# GPS.net
KiCad netlist of a schematic drawn in Altium Designer
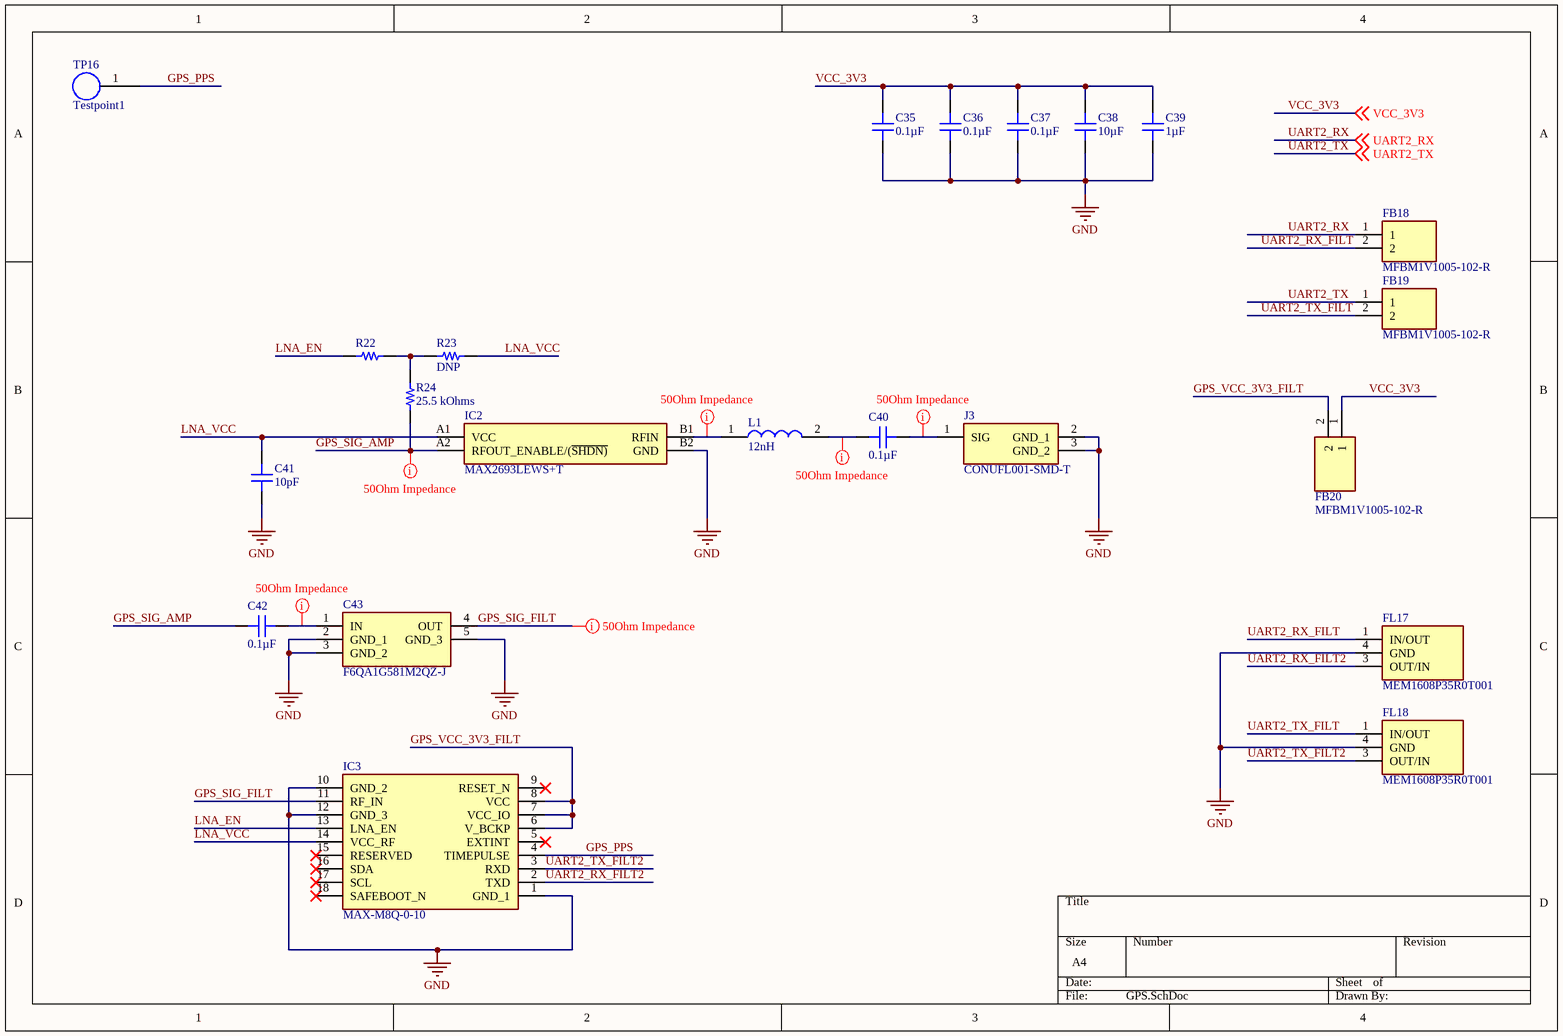
[diagram p0: GPS.SchDoc]

(export (version "E")
  (design (tool "Eeschema 10.0.6"))
  (components
    (comp (ref "C35")
      (value "0.1µF")
      (footprint "CAP 0402_1005")
      (description "CAP CER 0.1UF 6.3V X5R 0402")
      (fields (field (name "PART NUMBER") "C0402C104K9PACTU") (field (name "MANUFACTURER") "KEMET"))
      (libsource (lib "Celestial Altium Library - altium_library") (part "Capacitor"))
    )
    (comp (ref "C36")
      (value "0.1µF")
      (footprint "CAP 0402_1005")
      (description "CAP CER 0.1UF 6.3V X5R 0402")
      (fields (field (name "PART NUMBER") "C0402C104K9PACTU") (field (name "MANUFACTURER") "KEMET"))
      (libsource (lib "Celestial Altium Library - altium_library") (part "Capacitor"))
    )
    (comp (ref "C37")
      (value "0.1µF")
      (footprint "CAP 0402_1005")
      (description "CAP CER 0.1UF 6.3V X5R 0402")
      (fields (field (name "PART NUMBER") "C0402C104K9PACTU") (field (name "MANUFACTURER") "KEMET"))
      (libsource (lib "Celestial Altium Library - altium_library") (part "Capacitor"))
    )
    (comp (ref "C38")
      (value "10µF")
      (footprint "CAP 0402_1005")
      (description "CAP CER 10UF 6.3V X5R 0402")
      (fields (field (name "PART NUMBER") "C0402C106M9PAC7867") (field (name "MANUFACTURER") "KEMET"))
      (libsource (lib "Celestial Altium Library - altium_library") (part "Capacitor"))
    )
    (comp (ref "C39")
      (value "1µF")
      (footprint "CAP 0402_1005")
      (description "CAP CER 1UF 16V X5R 0402")
      (fields (field (name "PART NUMBER") "0402YD105KAT2A") (field (name "MANUFACTURER") "AVX Corporation"))
      (libsource (lib "Celestial Altium Library - altium_library") (part "Capacitor"))
    )
    (comp (ref "C40")
      (value "0.1µF")
      (footprint "CAP 0402_1005")
      (description "CAP CER 0.1UF 6.3V X5R 0402")
      (fields (field (name "PART NUMBER") "C0402C104K9PACTU") (field (name "MANUFACTURER") "KEMET"))
      (libsource (lib "Celestial Altium Library - altium_library") (part "Capacitor"))
    )
    (comp (ref "C41")
      (value "10pF")
      (footprint "CAP 0402_1005")
      (description "CAP CER 10PF 50V C0G/NP0 0402")
      (fields
        (field (name "PART NUMBER") "0402N100G500CT")
        (field (name "MANUFACTURER") "Walsin Technology Corporation")
      )
      (libsource (lib "Celestial Altium Library - altium_library") (part "Capacitor"))
    )
    (comp (ref "C42")
      (value "0.1µF")
      (footprint "CAP 0402_1005")
      (description "CAP CER 0.1UF 6.3V X5R 0402")
      (fields (field (name "PART NUMBER") "C0402C104K9PACTU") (field (name "MANUFACTURER") "KEMET"))
      (libsource (lib "Celestial Altium Library - altium_library") (part "Capacitor"))
    )
    (comp (ref "C43")
      (value "F6QA1G581M2QZ-J")
      (footprint "SamacSys:F6QA1G581M2QZJ")
      (description "Capacitor")
      (libsource (lib "SamacSys") (part "F6QA1G581M2QZ-J"))
    )
    (comp (ref "FB18")
      (value "MFBM1V1005-102-R")
      (footprint "SamacSys:BEADC1005X65N")
      (description "Ferrite Bead")
      (fields (field (name "MANUFACTURER_PART_NUMBER") "MFBM1V1005-101-R"))
      (libsource (lib "SamacSys") (part "MFBM1V1005-102-R"))
    )
    (comp (ref "FB19")
      (value "MFBM1V1005-102-R")
      (footprint "SamacSys:BEADC1005X65N")
      (description "Ferrite Bead")
      (fields (field (name "MANUFACTURER_PART_NUMBER") "MFBM1V1005-101-R"))
      (libsource (lib "SamacSys") (part "MFBM1V1005-102-R"))
    )
    (comp (ref "FB20")
      (value "MFBM1V1005-102-R")
      (footprint "SamacSys:BEADC1005X65N")
      (description "Ferrite Bead")
      (fields (field (name "MANUFACTURER_PART_NUMBER") "MFBM1V1005-101-R"))
      (libsource (lib "") (part "MFBM1V1005-102-R_1"))
    )
    (comp (ref "FL17")
      (value "MEM1608P35R0T001")
      (footprint "SamacSys:MEM1608P35R0T001")
      (description "Filter")
      (libsource (lib "SamacSys") (part "MEM1608P35R0T001"))
    )
    (comp (ref "FL18")
      (value "MEM1608P35R0T001")
      (footprint "SamacSys:MEM1608P35R0T001")
      (description "Filter")
      (libsource (lib "SamacSys") (part "MEM1608P35R0T001"))
    )
    (comp (ref "IC2")
      (value "MAX2693LEWS+T")
      (footprint "SamacSys:BGA4C40P2X2_84X84X69")
      (description "Integrated Circuit")
      (libsource (lib "*") (part "MAX2693LEWS+T"))
    )
    (comp (ref "IC3")
      (value "MAX-M8Q-0-10")
      (footprint "SamacSys:MAX-M8")
      (description "Integrated Circuit")
      (libsource (lib "SamacSys") (part "MAX-M8Q-0-10"))
    )
    (comp (ref "J3")
      (value "CONUFL001-SMD-T")
      (footprint "SamacSys:CONUFL001-SMD")
      (description "Connector")
      (fields (field (name "MOUSER2 PART NUMBER") "712-CONUFL001-SMD-T"))
      (libsource (lib "SamacSys") (part "CONUFL001-SMD-T"))
    )
    (comp (ref "L1")
      (value "12nH")
      (footprint "SamacSys:INDC1005X55N")
      (description "Inductor")
      (fields (field (name "MANUFACTURER_PART_NUMBER") "7447840112G"))
      (libsource (lib "*") (part "7447840112G"))
    )
    (comp (ref "R22")
      (value "~")
      (footprint "RES 0402_1005")
      (description "RES SMD 0 OHM JUMPER 1/16W 0402")
      (fields (field (name "PART NUMBER") "CRCW04020000Z0ED") (field (name "MANUFACTURER") "Vishay Dale"))
      (libsource (lib "Celestial Altium Library - altium_library") (part "Resistor"))
    )
    (comp (ref "R23")
      (value "~")
      (footprint "RES 0402_1005")
      (description "RES SMD 0 OHM JUMPER 1/16W 0402")
      (fields
        (field (name "PART NUMBER") "CRCW04020000Z0ED")
        (field (name "MANUFACTURER") "Vishay Dale")
        (field (name "ASSEMBLY INSTRUCTION") "DNP")
      )
      (libsource (lib "Celestial Altium Library - altium_library") (part "Resistor"))
    )
    (comp (ref "R24")
      (value "25.5 kOhms")
      (footprint "RES 0402_1005")
      (description "RES SMD 25.5K OHM 1% 1/16W 0402")
      (fields (field (name "PART NUMBER") "AC0402FR-0725K5L") (field (name "MANUFACTURER") "Yageo"))
      (libsource (lib "Celestial Altium Library - altium_library") (part "Resistor"))
    )
    (comp (ref "TP16")
      (value "Testpoint1")
      (footprint "Testpoint1")
      (libsource (lib "SamacSys") (part "Testpoint1"))
    )
  )
  (nets
    (net (code "1") (name "/GPS_PPS") (class "Default")
      (node (ref "IC3") (pin "4") (pinfunction "TIMEPULSE_4") (pintype "passive"))
      (node (ref "TP16") (pin "1") (pinfunction "1_1") (pintype "passive"))
    )
    (net (code "2") (name "/GPS_SIG_AMP") (class "Default")
      (node (ref "C42") (pin "2") (pinfunction "2_2") (pintype "passive"))
      (node (ref "IC2") (pin "A2") (pinfunction "RFOUT_ENABLE/(~{SHDN)}_A2") (pintype "passive"))
      (node (ref "R24") (pin "1") (pinfunction "1_1") (pintype "passive"))
    )
    (net (code "3") (name "/GPS_SIG_FILT") (class "Default")
      (node (ref "C43") (pin "4") (pinfunction "OUT_4") (pintype "passive"))
      (node (ref "IC3") (pin "11") (pinfunction "RF_IN_11") (pintype "passive"))
    )
    (net (code "4") (name "/GPS_VCC_3V3_FILT") (class "Default")
      (node (ref "FB20") (pin "2") (pinfunction "2_2") (pintype "passive"))
      (node (ref "IC3") (pin "6") (pinfunction "V_BCKP_6") (pintype "passive"))
      (node (ref "IC3") (pin "7") (pinfunction "VCC_IO_7") (pintype "passive"))
      (node (ref "IC3") (pin "8") (pinfunction "VCC_8") (pintype "passive"))
    )
    (net (code "5") (name "/LNA_EN") (class "Default")
      (node (ref "IC3") (pin "13") (pinfunction "LNA_EN_13") (pintype "passive"))
      (node (ref "R22") (pin "2") (pinfunction "2_2") (pintype "passive"))
    )
    (net (code "6") (name "/LNA_VCC") (class "Default")
      (node (ref "C41") (pin "2") (pinfunction "2_2") (pintype "passive"))
      (node (ref "IC2") (pin "A1") (pinfunction "VCC_A1") (pintype "passive"))
      (node (ref "IC3") (pin "14") (pinfunction "VCC_RF_14") (pintype "passive"))
      (node (ref "R23") (pin "1") (pinfunction "1_1") (pintype "passive"))
    )
    (net (code "7") (name "/UART2_RX_FILT") (class "Default")
      (node (ref "FB18") (pin "2") (pinfunction "2_2") (pintype "passive"))
      (node (ref "FL17") (pin "1") (pinfunction "IN/OUT_1") (pintype "passive"))
    )
    (net (code "8") (name "/UART2_RX_FILT2") (class "Default")
      (node (ref "FL17") (pin "3") (pinfunction "OUT/IN_3") (pintype "passive"))
      (node (ref "IC3") (pin "2") (pinfunction "TXD_2") (pintype "passive"))
    )
    (net (code "9") (name "/UART2_TX_FILT") (class "Default")
      (node (ref "FB19") (pin "2") (pinfunction "2_2") (pintype "passive"))
      (node (ref "FL18") (pin "1") (pinfunction "IN/OUT_1") (pintype "passive"))
    )
    (net (code "10") (name "/UART2_TX_FILT2") (class "Default")
      (node (ref "FL18") (pin "3") (pinfunction "OUT/IN_3") (pintype "passive"))
      (node (ref "IC3") (pin "3") (pinfunction "RXD_3") (pintype "passive"))
    )
    (net (code "11") (name "GND") (class "Default")
      (node (ref "C35") (pin "1") (pinfunction "1_1") (pintype "passive"))
      (node (ref "C36") (pin "1") (pinfunction "1_1") (pintype "passive"))
      (node (ref "C37") (pin "1") (pinfunction "1_1") (pintype "passive"))
      (node (ref "C38") (pin "1") (pinfunction "1_1") (pintype "passive"))
      (node (ref "C39") (pin "1") (pinfunction "1_1") (pintype "passive"))
      (node (ref "C41") (pin "1") (pinfunction "1_1") (pintype "passive"))
      (node (ref "C43") (pin "2") (pinfunction "GND_1_2") (pintype "passive"))
      (node (ref "C43") (pin "3") (pinfunction "GND_2_3") (pintype "passive"))
      (node (ref "C43") (pin "5") (pinfunction "GND_3_5") (pintype "passive"))
      (node (ref "FL17") (pin "4") (pinfunction "GND_4") (pintype "passive"))
      (node (ref "FL18") (pin "4") (pinfunction "GND_4") (pintype "passive"))
      (node (ref "IC2") (pin "B2") (pinfunction "GND_B2") (pintype "passive"))
      (node (ref "IC3") (pin "1") (pinfunction "GND_1_1") (pintype "passive"))
      (node (ref "IC3") (pin "10") (pinfunction "GND_2_10") (pintype "passive"))
      (node (ref "IC3") (pin "12") (pinfunction "GND_3_12") (pintype "passive"))
      (node (ref "J3") (pin "2") (pinfunction "GND_1_2") (pintype "passive"))
      (node (ref "J3") (pin "3") (pinfunction "GND_2_3") (pintype "passive"))
    )
    (net (code "12") (name "Net-(C40-Pad2)") (class "Default")
      (node (ref "C40") (pin "2") (pinfunction "2_2") (pintype "passive"))
      (node (ref "L1") (pin "2") (pinfunction "2_2") (pintype "passive"))
    )
    (net (code "13") (name "Net-(C43-IN)") (class "Default")
      (node (ref "C42") (pin "1") (pinfunction "1_1") (pintype "passive"))
      (node (ref "C43") (pin "1") (pinfunction "IN_1") (pintype "passive"))
    )
    (net (code "14") (name "Net-(IC2-RFIN)") (class "Default")
      (node (ref "IC2") (pin "B1") (pinfunction "RFIN_B1") (pintype "passive"))
      (node (ref "L1") (pin "1") (pinfunction "1_1") (pintype "passive"))
    )
    (net (code "15") (name "Net-(J3-SIG)") (class "Default")
      (node (ref "C40") (pin "1") (pinfunction "1_1") (pintype "passive"))
      (node (ref "J3") (pin "1") (pinfunction "SIG_1") (pintype "passive"))
    )
    (net (code "16") (name "Net-(R22-Pad1)") (class "Default")
      (node (ref "R22") (pin "1") (pinfunction "1_1") (pintype "passive"))
      (node (ref "R23") (pin "2") (pinfunction "2_2") (pintype "passive"))
      (node (ref "R24") (pin "2") (pinfunction "2_2") (pintype "passive"))
    )
    (net (code "17") (name "UART2_RX") (class "Default")
      (node (ref "FB18") (pin "1") (pinfunction "1_1") (pintype "passive"))
    )
    (net (code "18") (name "UART2_TX") (class "Default")
      (node (ref "FB19") (pin "1") (pinfunction "1_1") (pintype "passive"))
    )
    (net (code "19") (name "VCC_3V3") (class "Default")
      (node (ref "C35") (pin "2") (pinfunction "2_2") (pintype "passive"))
      (node (ref "C36") (pin "2") (pinfunction "2_2") (pintype "passive"))
      (node (ref "C37") (pin "2") (pinfunction "2_2") (pintype "passive"))
      (node (ref "C38") (pin "2") (pinfunction "2_2") (pintype "passive"))
      (node (ref "C39") (pin "2") (pinfunction "2_2") (pintype "passive"))
      (node (ref "FB20") (pin "1") (pinfunction "1_1") (pintype "passive"))
    )
    (net (code "20") (name "unconnected-(IC3-EXTINT-Pad5)") (class "Default")
      (node (ref "IC3") (pin "5") (pinfunction "EXTINT_5") (pintype "passive+no_connect"))
    )
    (net (code "21") (name "unconnected-(IC3-RESERVED-Pad15)") (class "Default")
      (node (ref "IC3") (pin "15") (pinfunction "RESERVED_15") (pintype "passive+no_connect"))
    )
    (net (code "22") (name "unconnected-(IC3-RESET_N-Pad9)") (class "Default")
      (node (ref "IC3") (pin "9") (pinfunction "RESET_N_9") (pintype "passive+no_connect"))
    )
    (net (code "23") (name "unconnected-(IC3-SAFEBOOT_N-Pad18)") (class "Default")
      (node (ref "IC3") (pin "18") (pinfunction "SAFEBOOT_N_18") (pintype "passive+no_connect"))
    )
    (net (code "24") (name "unconnected-(IC3-SCL-Pad17)") (class "Default")
      (node (ref "IC3") (pin "17") (pinfunction "SCL_17") (pintype "passive+no_connect"))
    )
    (net (code "25") (name "unconnected-(IC3-SDA-Pad16)") (class "Default")
      (node (ref "IC3") (pin "16") (pinfunction "SDA_16") (pintype "passive+no_connect"))
    )
  )
)
